# Ups_Design2.net
KiCad netlist of a schematic drawn in Altium Designer
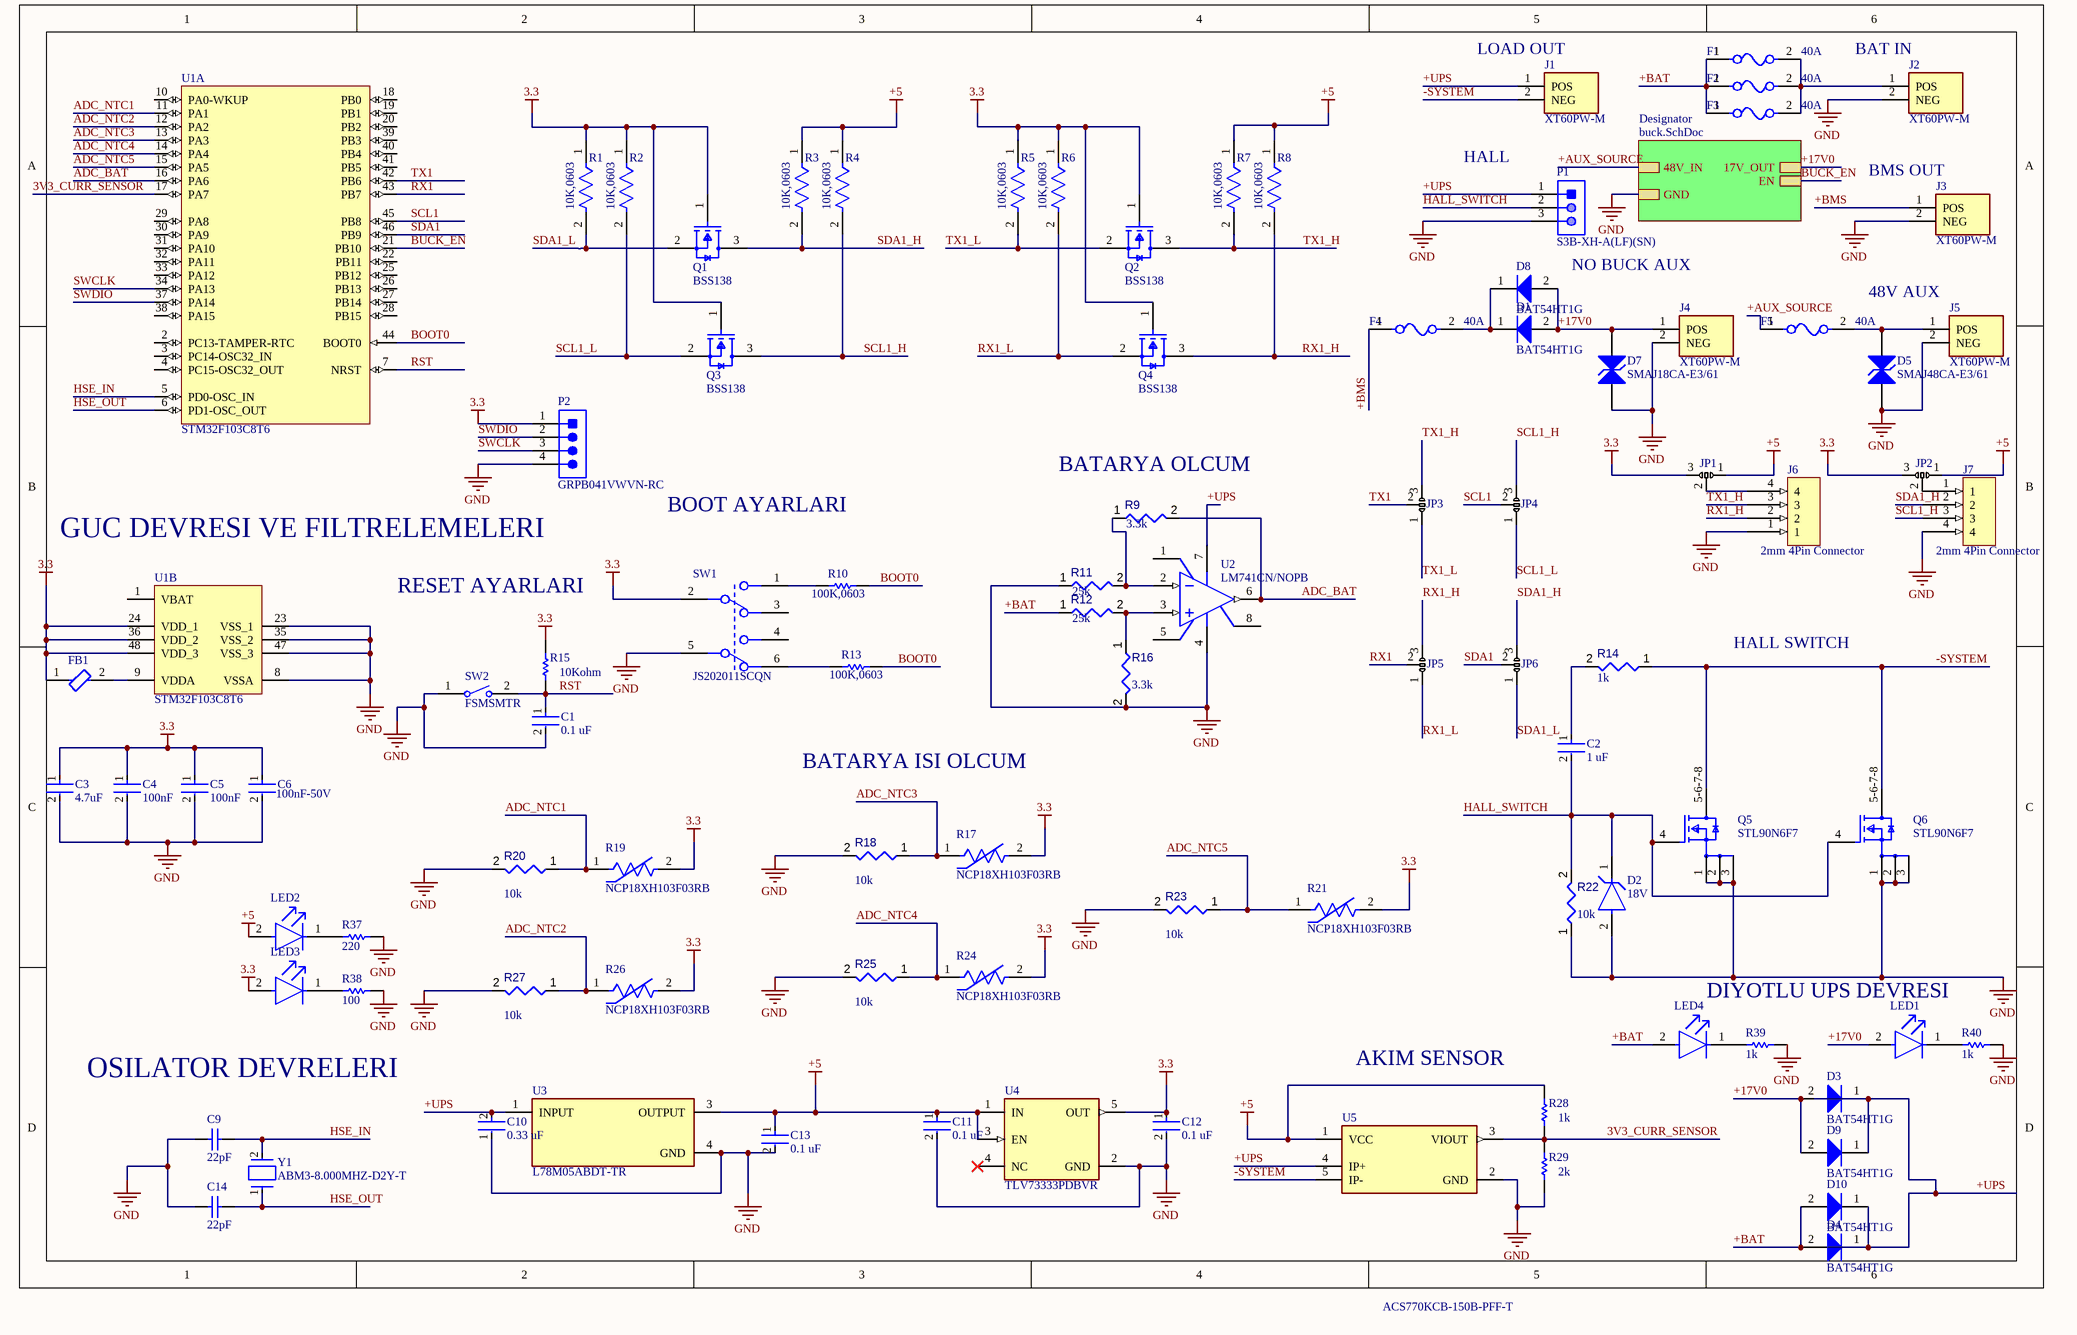
[diagram p0: Ups_Design2.SchDoc]

(export (version "E")
  (design (tool "Eeschema 10.0.6"))
  (components
    (comp (ref "C1")
      (value "0.1 uF")
      (footprint "FP-GCM188-0_1-IPC_B")
      (description "Ceramic Capacitor for Automotive 100nF  ±10% 50VDC X8L 0603 Paper T/R")
      (fields (field (name "TOLERANCE") "10%") (field (name "VOLTAGE") "50V"))
      (libsource (lib "Altium Content Vault") (part "02cd4be3c70576c341d710602a673aa"))
    )
    (comp (ref "C2")
      (value "1 uF")
      (footprint "FP-0603-L_1_6_0_15-W_0_8-IPC_C")
      (description "Ceramic Capacitor General Use 1uF ±10% 50V X7R 0603")
      (fields (field (name "TOLERANCE") "10%"))
      (libsource (lib "Altium Content Vault") (part "11868f565c42a9108669ba33697ecf6"))
    )
    (comp (ref "C3")
      (value "4.7uF")
      (footprint "FP-GRM188-0_2-IPC_C")
      (description "Chip Multilayer Ceramic Capacitors for General Purpose, 0603, 4.7uF, X5R, 15%, 10%, 35V")
      (fields (field (name "VOLTAGE") "35V") (field (name "TOLERANCE") "10%"))
      (libsource (lib "Altium Content Vault") (part "11868f565c42a9108669ba33697ecf6"))
    )
    (comp (ref "C4")
      (value "100nF")
      (footprint "FP-CGA3E-0_3-0_1-IPC_A")
      (description "Cap Ceramic 100nF 50V X7R 10% Pad SMD 0603 +125°C Automotive T/R")
      (fields (field (name "TOLERANCE") "10%") (field (name "VOLTAGE") "50V"))
      (libsource (lib "Altium Content Vault") (part "b4654b650e69147ec39a6b967a45e02"))
    )
    (comp (ref "C5")
      (value "100nF")
      (footprint "FP-CGA3E-0_3-0_1-IPC_A")
      (description "Cap Ceramic 100nF 50V X7R 10% Pad SMD 0603 +125°C Automotive T/R")
      (fields (field (name "TOLERANCE") "10%") (field (name "VOLTAGE") "50V"))
      (libsource (lib "Altium Content Vault") (part "b4654b650e69147ec39a6b967a45e02"))
    )
    (comp (ref "C6")
      (value "100nF-50V")
      (footprint "FP-CGA3E-0_3-0_1-IPC_A")
      (description "Cap Ceramic 100nF 50V X7R 10% Pad SMD 0603 +125°C Automotive T/R")
      (fields (field (name "TOLERANCE") "10%") (field (name "VOLTAGE") "50V"))
      (libsource (lib "Altium Content Vault") (part "b4654b650e69147ec39a6b967a45e02"))
    )
    (comp (ref "C9")
      (value "22pF")
      (footprint "CAPC1608X73X35LL10T15")
      (fields
        (field (name "PART NUMBER") "06033J220GBSTR")
        (field (name "MANUFACTURER") "AVX Interconnect / Elco")
      )
      (libsource (lib "Altium Content Vault") (part "CAP"))
    )
    (comp (ref "C10")
      (value "0.33 uF")
      (footprint "FP-C1608-080-0_1-IPC_B")
      (description "Multilayer Ceramic Capacitors 330nF ±10% 50V X7R SMD 0603")
      (fields (field (name "TOLERANCE") "10%") (field (name "VOLTAGE") "50V"))
      (libsource (lib "Altium Content Vault") (part "236180d848d6139a670b325ea6854c9"))
    )
    (comp (ref "C11")
      (value "0.1 uF")
      (footprint "FP-GCM188-0_1-IPC_B")
      (description "Ceramic Capacitor for Automotive 100nF  ±10% 50VDC X8L 0603 Paper T/R")
      (fields (field (name "TOLERANCE") "10%") (field (name "VOLTAGE") "50V"))
      (libsource (lib "Altium Content Vault") (part "02cd4be3c70576c341d710602a673aa"))
    )
    (comp (ref "C12")
      (value "0.1 uF")
      (footprint "FP-GCM188-0_1-IPC_B")
      (description "Ceramic Capacitor for Automotive 100nF  ±10% 50VDC X8L 0603 Paper T/R")
      (fields (field (name "TOLERANCE") "10%") (field (name "VOLTAGE") "50V"))
      (libsource (lib "Altium Content Vault") (part "02cd4be3c70576c341d710602a673aa"))
    )
    (comp (ref "C13")
      (value "0.1 uF")
      (footprint "FP-GCM188-0_1-IPC_B")
      (description "Ceramic Capacitor for Automotive 100nF  ±10% 50VDC X8L 0603 Paper T/R")
      (fields (field (name "TOLERANCE") "10%") (field (name "VOLTAGE") "50V"))
      (libsource (lib "Altium Content Vault") (part "02cd4be3c70576c341d710602a673aa"))
    )
    (comp (ref "C14")
      (value "22pF")
      (footprint "CAPC1608X73X35LL10T15")
      (fields
        (field (name "PART NUMBER") "06033J220GBSTR")
        (field (name "MANUFACTURER") "AVX Interconnect / Elco")
      )
      (libsource (lib "Altium Content Vault") (part "CAP"))
    )
    (comp (ref "D1")
      (value "BAT54HT1G")
      (footprint "ONSC-SOD-323-2-477-02_V")
      (description "Schottky Barrier Diode, 2-Pin SOD-323, Pb-Free, Tape and Reel")
      (fields (field (name "MANUFACTURER") "On Semiconductor"))
      (libsource (lib "Altium Content Vault") (part "ONSC-D-K1A2-2"))
    )
    (comp (ref "D2")
      (value "18V")
      (footprint "FP-SOD123-MFG")
      (description "DIODE ZENER 18V 500MW SOD123")
      (fields
        (field (name "OCTOPART") "https://octopart.com/bzt52c18-7-f-diodes+inc.-326572")
        (field (name "MANUFACTURER") "Diodes Inc.")
      )
      (libsource (lib "Altium Content Vault") (part "f813f71cba58e380607f5dd3caf9714"))
    )
    (comp (ref "D3")
      (value "BAT54HT1G")
      (footprint "ONSC-SOD-323-2-477-02_V")
      (description "Schottky Barrier Diode, 2-Pin SOD-323, Pb-Free, Tape and Reel")
      (fields (field (name "MANUFACTURER") "On Semiconductor"))
      (libsource (lib "Altium Content Vault") (part "ONSC-D-K1A2-2"))
    )
    (comp (ref "D4")
      (value "BAT54HT1G")
      (footprint "ONSC-SOD-323-2-477-02_V")
      (description "Schottky Barrier Diode, 2-Pin SOD-323, Pb-Free, Tape and Reel")
      (fields (field (name "MANUFACTURER") "On Semiconductor"))
      (libsource (lib "Altium Content Vault") (part "ONSC-D-K1A2-2"))
    )
    (comp (ref "D5")
      (value "SMAJ48CA-E3/61")
      (footprint "VISH-DO-214AC-2_M")
      (fields (field (name "MANUFACTURER") "Vishay Semiconductor"))
      (libsource (lib "Altium Content Vault") (part "VISH-A1A2-2"))
    )
    (comp (ref "D7")
      (value "SMAJ18CA-E3/61")
      (footprint "VISH-DO-214AC-2_L")
      (fields (field (name "MANUFACTURER") "Vishay Semiconductor"))
      (libsource (lib "Altium Content Vault") (part "VISH-A1A2-2"))
    )
    (comp (ref "D8")
      (value "BAT54HT1G")
      (footprint "ONSC-SOD-323-2-477-02_V")
      (description "Schottky Barrier Diode, 2-Pin SOD-323, Pb-Free, Tape and Reel")
      (fields (field (name "MANUFACTURER") "On Semiconductor"))
      (libsource (lib "Altium Content Vault") (part "ONSC-D-K1A2-2"))
    )
    (comp (ref "D9")
      (value "BAT54HT1G")
      (footprint "ONSC-SOD-323-2-477-02_V")
      (description "Schottky Barrier Diode, 2-Pin SOD-323, Pb-Free, Tape and Reel")
      (fields (field (name "MANUFACTURER") "On Semiconductor"))
      (libsource (lib "Altium Content Vault") (part "ONSC-D-K1A2-2"))
    )
    (comp (ref "D10")
      (value "BAT54HT1G")
      (footprint "ONSC-SOD-323-2-477-02_V")
      (description "Schottky Barrier Diode, 2-Pin SOD-323, Pb-Free, Tape and Reel")
      (fields (field (name "MANUFACTURER") "On Semiconductor"))
      (libsource (lib "Altium Content Vault") (part "ONSC-D-K1A2-2"))
    )
    (comp (ref "F1")
      (value "40A")
      (footprint "FP-0456040_DR-MFG")
      (description "FUSE BOARD MOUNT 40A 60VDC 2SMD")
      (fields
        (field (name "MANUFACTURER PART NUMBER") "0456040.DR")
        (field (name "OCTOPART") "https://octopart.com/0456040.dr-littelfuse-18189767")
      )
      (libsource (lib "Altium Content Vault") (part "5bcf9b9f640e542cf0359d10258e979"))
    )
    (comp (ref "F2")
      (value "40A")
      (footprint "FP-0456040_DR-MFG")
      (description "FUSE BOARD MOUNT 40A 60VDC 2SMD")
      (fields
        (field (name "MANUFACTURER PART NUMBER") "0456040.DR")
        (field (name "OCTOPART") "https://octopart.com/0456040.dr-littelfuse-18189767")
      )
      (libsource (lib "Altium Content Vault") (part "5bcf9b9f640e542cf0359d10258e979"))
    )
    (comp (ref "F3")
      (value "40A")
      (footprint "FP-0456040_DR-MFG")
      (description "FUSE BOARD MOUNT 40A 60VDC 2SMD")
      (fields
        (field (name "MANUFACTURER PART NUMBER") "0456040.DR")
        (field (name "OCTOPART") "https://octopart.com/0456040.dr-littelfuse-18189767")
      )
      (libsource (lib "Altium Content Vault") (part "5bcf9b9f640e542cf0359d10258e979"))
    )
    (comp (ref "F4")
      (value "40A")
      (footprint "FP-0456040_DR-MFG")
      (description "FUSE BOARD MOUNT 40A 60VDC 2SMD")
      (fields
        (field (name "MANUFACTURER PART NUMBER") "0456040.DR")
        (field (name "OCTOPART") "https://octopart.com/0456040.dr-littelfuse-18189767")
      )
      (libsource (lib "Altium Content Vault") (part "5bcf9b9f640e542cf0359d10258e979"))
    )
    (comp (ref "F5")
      (value "40A")
      (footprint "FP-0456040_DR-MFG")
      (description "FUSE BOARD MOUNT 40A 60VDC 2SMD")
      (fields
        (field (name "MANUFACTURER PART NUMBER") "0456040.DR")
        (field (name "OCTOPART") "https://octopart.com/0456040.dr-littelfuse-18189767")
      )
      (libsource (lib "Altium Content Vault") (part "5bcf9b9f640e542cf0359d10258e979"))
    )
    (comp (ref "FB1")
      (value "BLM18SG221TN1D")
      (footprint "FP-BLM18-0_15-t0_5-IPC_A")
      (description "Chip Ferrite Bead, 0603, 220Ω @ 100MHz, 25%, 0.04Ω, 2.5A")
      (fields (field (name "TOLERANCE") "25%"))
      (libsource (lib "Altium Content Vault") (part "5f30dd21d616792df468990f7003faa"))
    )
    (comp (ref "J1")
      (value "XT60PW-M")
      (footprint "AMASS_XT60PW-M")
      (description "Socket, DC supply, male, PIN: 2")
      (fields (field (name "MF") "AMASS"))
      (libsource (lib "XT60PW-M") (part "XT60PW-M"))
    )
    (comp (ref "J2")
      (value "XT60PW-M")
      (footprint "AMASS_XT60PW-M")
      (description "Socket, DC supply, male, PIN: 2")
      (fields (field (name "MF") "AMASS"))
      (libsource (lib "XT60PW-M") (part "XT60PW-M"))
    )
    (comp (ref "J3")
      (value "XT60PW-M")
      (footprint "AMASS_XT60PW-M")
      (description "Socket, DC supply, male, PIN: 2")
      (fields (field (name "MF") "AMASS"))
      (libsource (lib "XT60PW-M") (part "XT60PW-M"))
    )
    (comp (ref "J4")
      (value "XT60PW-M")
      (footprint "AMASS_XT60PW-M")
      (description "Socket, DC supply, male, PIN: 2")
      (fields (field (name "MF") "AMASS"))
      (libsource (lib "XT60PW-M") (part "XT60PW-M"))
    )
    (comp (ref "J5")
      (value "XT60PW-M")
      (footprint "AMASS_XT60PW-M")
      (description "Socket, DC supply, male, PIN: 2")
      (fields (field (name "MF") "AMASS"))
      (libsource (lib "XT60PW-M") (part "XT60PW-M"))
    )
    (comp (ref "J6")
      (value "2mm 4Pin Connector")
      (footprint "New footprint 1")
      (libsource (lib "İtü Rov") (part "New symbol 1"))
    )
    (comp (ref "J7")
      (value "2mm 4Pin Connector")
      (footprint "New footprint 1")
      (libsource (lib "") (part "New symbol 1_1"))
    )
    (comp (ref "JP1")
      (value "Jumper Pad 3P")
      (footprint "Jumper Pad 3P-Footprint-1")
      (description "3Pin Jumper Pad SWH")
      (libsource (lib "İtü Rov") (part "Jumper Pad 3P-Symbol-1"))
    )
    (comp (ref "JP2")
      (value "Jumper Pad 3P")
      (footprint "Jumper Pad 3P-Footprint-1")
      (description "3Pin Jumper Pad SWH")
      (libsource (lib "İtü Rov") (part "Jumper Pad 3P-Symbol-1"))
    )
    (comp (ref "JP3")
      (value "Jumper Pad 3P")
      (footprint "Jumper Pad 3P-Footprint-1")
      (description "3Pin Jumper Pad SWH")
      (libsource (lib "İtü Rov") (part "Jumper Pad 3P-Symbol-1"))
    )
    (comp (ref "JP4")
      (value "Jumper Pad 3P")
      (footprint "Jumper Pad 3P-Footprint-1")
      (description "3Pin Jumper Pad SWH")
      (libsource (lib "İtü Rov") (part "Jumper Pad 3P-Symbol-1"))
    )
    (comp (ref "JP5")
      (value "Jumper Pad 3P")
      (footprint "Jumper Pad 3P-Footprint-1")
      (description "3Pin Jumper Pad SWH")
      (libsource (lib "İtü Rov") (part "Jumper Pad 3P-Symbol-1"))
    )
    (comp (ref "JP6")
      (value "Jumper Pad 3P")
      (footprint "Jumper Pad 3P-Footprint-1")
      (description "3Pin Jumper Pad SWH")
      (libsource (lib "İtü Rov") (part "Jumper Pad 3P-Symbol-1"))
    )
    (comp (ref "LED1")
      (value "TLMO1000-GS08")
      (footprint "FP-6_541-5056_01-4-MFG")
      (description "LED ORANGE 0603 SMD")
      (fields
        (field (name "OCTOPART") "https://octopart.com/tlmo1000-gs08-vishay-41955669")
        (field (name "MANUFACTURER") "Vishay")
      )
      (libsource (lib "Altium Content Vault") (part "8706943c75ba83719d021d2fdc84c58"))
    )
    (comp (ref "LED2")
      (value "TLMO1000-GS08")
      (footprint "FP-6_541-5056_01-4-MFG")
      (description "LED ORANGE 0603 SMD")
      (fields
        (field (name "OCTOPART") "https://octopart.com/tlmo1000-gs08-vishay-41955669")
        (field (name "MANUFACTURER") "Vishay")
      )
      (libsource (lib "Altium Content Vault") (part "8706943c75ba83719d021d2fdc84c58"))
    )
    (comp (ref "LED3")
      (value "TLMO1000-GS08")
      (footprint "FP-6_541-5056_01-4-MFG")
      (description "LED ORANGE 0603 SMD")
      (fields
        (field (name "OCTOPART") "https://octopart.com/tlmo1000-gs08-vishay-41955669")
        (field (name "MANUFACTURER") "Vishay")
      )
      (libsource (lib "Altium Content Vault") (part "8706943c75ba83719d021d2fdc84c58"))
    )
    (comp (ref "LED4")
      (value "TLMO1000-GS08")
      (footprint "FP-6_541-5056_01-4-MFG")
      (description "LED ORANGE 0603 SMD")
      (fields
        (field (name "OCTOPART") "https://octopart.com/tlmo1000-gs08-vishay-41955669")
        (field (name "MANUFACTURER") "Vishay")
      )
      (libsource (lib "Altium Content Vault") (part "8706943c75ba83719d021d2fdc84c58"))
    )
    (comp (ref "P1")
      (value "S3B-XH-A(LF)(SN)")
      (footprint "JST-S3B-XH-A(LF)(SN)_V")
      (libsource (lib "Altium Content Vault") (part "CN-1P-M-R3"))
    )
    (comp (ref "P2")
      (value "GRPB041VWVN-RC")
      (footprint "SLIN-GRPB041VWVN-RC_V")
      (fields (field (name "MANUFACTURER") "Sullins"))
      (libsource (lib "Altium Content Vault") (part "CN-1P-M-R4"))
    )
    (comp (ref "Q1")
      (value "BSS138")
      (footprint "FP-318-08-IPC_B")
      (description "MOSFET N-CH 50V 220MA SOT-23")
      (libsource (lib "Altium Content Vault") (part "3b9c635fedb024a5347a57b145af9cc"))
    )
    (comp (ref "Q2")
      (value "BSS138")
      (footprint "FP-318-08-IPC_B")
      (description "MOSFET N-CH 50V 220MA SOT-23")
      (libsource (lib "Altium Content Vault") (part "3b9c635fedb024a5347a57b145af9cc"))
    )
    (comp (ref "Q3")
      (value "BSS138")
      (footprint "FP-318-08-IPC_B")
      (description "MOSFET N-CH 50V 220MA SOT-23")
      (libsource (lib "Altium Content Vault") (part "3b9c635fedb024a5347a57b145af9cc"))
    )
    (comp (ref "Q4")
      (value "BSS138")
      (footprint "FP-318-08-IPC_B")
      (description "MOSFET N-CH 50V 220MA SOT-23")
      (libsource (lib "Altium Content Vault") (part "3b9c635fedb024a5347a57b145af9cc"))
    )
    (comp (ref "Q5")
      (value "STL90N6F7")
      (footprint "FP-8472137_SUBCON_998G-MFG")
      (description "MOSFET N-CH 60V 90A POWERFLAT")
      (libsource (lib "Altium Content Vault") (part "7382af88e928fdc71488234cfaaf11c"))
    )
    (comp (ref "Q6")
      (value "STL90N6F7")
      (footprint "FP-8472137_SUBCON_998G-MFG")
      (description "MOSFET N-CH 60V 90A POWERFLAT")
      (libsource (lib "Altium Content Vault") (part "7382af88e928fdc71488234cfaaf11c"))
    )
    (comp (ref "R1")
      (value "10K,0603")
      (footprint "FP-ERJ3G-IPC_C")
      (description "RES SMD 10K OHM 5% 1/10W 0603")
      (fields (field (name "TOLERANCE") "5%"))
      (libsource (lib "Altium Content Vault") (part "1029c3af85768c4190bb7ad29bc67b5"))
    )
    (comp (ref "R2")
      (value "10K,0603")
      (footprint "FP-ERJ3G-IPC_C")
      (description "RES SMD 10K OHM 5% 1/10W 0603")
      (fields (field (name "TOLERANCE") "5%"))
      (libsource (lib "Altium Content Vault") (part "1029c3af85768c4190bb7ad29bc67b5"))
    )
    (comp (ref "R3")
      (value "10K,0603")
      (footprint "FP-ERJ3G-IPC_C")
      (description "RES SMD 10K OHM 5% 1/10W 0603")
      (fields (field (name "TOLERANCE") "5%"))
      (libsource (lib "Altium Content Vault") (part "1029c3af85768c4190bb7ad29bc67b5"))
    )
    (comp (ref "R4")
      (value "10K,0603")
      (footprint "FP-ERJ3G-IPC_C")
      (description "RES SMD 10K OHM 5% 1/10W 0603")
      (fields (field (name "TOLERANCE") "5%"))
      (libsource (lib "Altium Content Vault") (part "1029c3af85768c4190bb7ad29bc67b5"))
    )
    (comp (ref "R5")
      (value "10K,0603")
      (footprint "FP-ERJ3G-IPC_C")
      (description "RES SMD 10K OHM 5% 1/10W 0603")
      (fields (field (name "TOLERANCE") "5%"))
      (libsource (lib "Altium Content Vault") (part "1029c3af85768c4190bb7ad29bc67b5"))
    )
    (comp (ref "R6")
      (value "10K,0603")
      (footprint "FP-ERJ3G-IPC_C")
      (description "RES SMD 10K OHM 5% 1/10W 0603")
      (fields (field (name "TOLERANCE") "5%"))
      (libsource (lib "Altium Content Vault") (part "1029c3af85768c4190bb7ad29bc67b5"))
    )
    (comp (ref "R7")
      (value "10K,0603")
      (footprint "FP-ERJ3G-IPC_C")
      (description "RES SMD 10K OHM 5% 1/10W 0603")
      (fields (field (name "TOLERANCE") "5%"))
      (libsource (lib "Altium Content Vault") (part "1029c3af85768c4190bb7ad29bc67b5"))
    )
    (comp (ref "R8")
      (value "10K,0603")
      (footprint "FP-ERJ3G-IPC_C")
      (description "RES SMD 10K OHM 5% 1/10W 0603")
      (fields (field (name "TOLERANCE") "5%"))
      (libsource (lib "Altium Content Vault") (part "1029c3af85768c4190bb7ad29bc67b5"))
    )
    (comp (ref "R9")
      (value "3.3k")
      (footprint "RESC1608X55X25ML10T15")
      (description "Chip Resistor, 1 KOhm, +/-1%, 0.1 W, -55 to 155 degC, 0603 (1608 Metric)")
      (fields (field (name "POWER") "100mW") (field (name "TOLERANCE") "1%"))
      (libsource (lib "İtü Rov") (part "RES-2"))
    )
    (comp (ref "R10")
      (value "100K,0603")
      (footprint "RESC1608X100X25ML20T15")
      (fields (field (name "MANUFACTURER") "Vishay Dale") (field (name "PART NUMBER") "NTHS0603N01N1003JE"))
      (libsource (lib "Altium Content Vault") (part "RES"))
    )
    (comp (ref "R11")
      (value "25k")
      (footprint "RESC1608X55X25ML10T15")
      (description "Chip Resistor, 1 KOhm, +/-1%, 0.1 W, -55 to 155 degC, 0603 (1608 Metric)")
      (fields (field (name "POWER") "100mW") (field (name "TOLERANCE") "1%"))
      (libsource (lib "İtü Rov") (part "RES-2"))
    )
    (comp (ref "R12")
      (value "25k")
      (footprint "RESC1608X55X25ML10T15")
      (description "Chip Resistor, 1 KOhm, +/-1%, 0.1 W, -55 to 155 degC, 0603 (1608 Metric)")
      (fields (field (name "POWER") "100mW") (field (name "TOLERANCE") "1%"))
      (libsource (lib "İtü Rov") (part "RES-2"))
    )
    (comp (ref "R13")
      (value "100K,0603")
      (footprint "RESC1608X100X25ML20T15")
      (fields (field (name "MANUFACTURER") "Vishay Dale") (field (name "PART NUMBER") "NTHS0603N01N1003JE"))
      (libsource (lib "Altium Content Vault") (part "RES"))
    )
    (comp (ref "R14")
      (value "1k")
      (footprint "RESC1608X55X25ML10T15")
      (description "Chip Resistor, 1 KOhm, +/-1%, 0.1 W, -55 to 155 degC, 0603 (1608 Metric)")
      (fields (field (name "POWER") "100mW") (field (name "TOLERANCE") "1%"))
      (libsource (lib "İtü Rov") (part "RES-2"))
    )
    (comp (ref "R15")
      (value "10Kohm")
      (footprint "RESC1608X55X25ML10T15")
      (fields (field (name "MANUFACTURER") "Yageo") (field (name "PART NUMBER") "RC0603JR-070RA"))
      (libsource (lib "Altium Content Vault") (part "RES"))
    )
    (comp (ref "R16")
      (value "3.3k")
      (footprint "RESC1608X55X25ML10T15")
      (description "Chip Resistor, 1 KOhm, +/-1%, 0.1 W, -55 to 155 degC, 0603 (1608 Metric)")
      (fields (field (name "POWER") "100mW") (field (name "TOLERANCE") "1%"))
      (libsource (lib "İtü Rov") (part "RES-2"))
    )
    (comp (ref "R17")
      (value "NCP18XH103F03RB")
      (footprint "FP-NCP18-0_15-IPC_A")
      (description "NTC Thermistor for Temperature Sensor, 0603, 10kΩ, 1%, 0.1mA, 5V")
      (fields (field (name "TOLERANCE") "1%"))
      (libsource (lib "Altium Content Vault") (part "3b148a6ebabc5fb4d708a66c052d352"))
    )
    (comp (ref "R18")
      (value "10k")
      (footprint "RESC1608X55X25ML10T15")
      (description "Chip Resistor, 1 KOhm, +/-1%, 0.1 W, -55 to 155 degC, 0603 (1608 Metric)")
      (fields (field (name "POWER") "100mW") (field (name "TOLERANCE") "1%"))
      (libsource (lib "İtü Rov") (part "RES-2"))
    )
    (comp (ref "R19")
      (value "NCP18XH103F03RB")
      (footprint "FP-NCP18-0_15-IPC_A")
      (description "NTC Thermistor for Temperature Sensor, 0603, 10kΩ, 1%, 0.1mA, 5V")
      (fields (field (name "TOLERANCE") "1%"))
      (libsource (lib "Altium Content Vault") (part "3b148a6ebabc5fb4d708a66c052d352"))
    )
    (comp (ref "R20")
      (value "10k")
      (footprint "RESC1608X55X25ML10T15")
      (description "Chip Resistor, 1 KOhm, +/-1%, 0.1 W, -55 to 155 degC, 0603 (1608 Metric)")
      (fields (field (name "POWER") "100mW") (field (name "TOLERANCE") "1%"))
      (libsource (lib "İtü Rov") (part "RES-2"))
    )
    (comp (ref "R21")
      (value "NCP18XH103F03RB")
      (footprint "FP-NCP18-0_15-IPC_A")
      (description "NTC Thermistor for Temperature Sensor, 0603, 10kΩ, 1%, 0.1mA, 5V")
      (fields (field (name "TOLERANCE") "1%"))
      (libsource (lib "Altium Content Vault") (part "3b148a6ebabc5fb4d708a66c052d352"))
    )
    (comp (ref "R22")
      (value "10k")
      (footprint "RESC1608X55X25ML10T15")
      (description "Chip Resistor, 1 KOhm, +/-1%, 0.1 W, -55 to 155 degC, 0603 (1608 Metric)")
      (fields (field (name "POWER") "100mW") (field (name "TOLERANCE") "1%"))
      (libsource (lib "İtü Rov") (part "RES-2"))
    )
    (comp (ref "R23")
      (value "10k")
      (footprint "RESC1608X55X25ML10T15")
      (description "Chip Resistor, 1 KOhm, +/-1%, 0.1 W, -55 to 155 degC, 0603 (1608 Metric)")
      (fields (field (name "POWER") "100mW") (field (name "TOLERANCE") "1%"))
      (libsource (lib "İtü Rov") (part "RES-2"))
    )
    (comp (ref "R24")
      (value "NCP18XH103F03RB")
      (footprint "FP-NCP18-0_15-IPC_A")
      (description "NTC Thermistor for Temperature Sensor, 0603, 10kΩ, 1%, 0.1mA, 5V")
      (fields (field (name "TOLERANCE") "1%"))
      (libsource (lib "Altium Content Vault") (part "3b148a6ebabc5fb4d708a66c052d352"))
    )
    (comp (ref "R25")
      (value "10k")
      (footprint "RESC1608X55X25ML10T15")
      (description "Chip Resistor, 1 KOhm, +/-1%, 0.1 W, -55 to 155 degC, 0603 (1608 Metric)")
      (fields (field (name "POWER") "100mW") (field (name "TOLERANCE") "1%"))
      (libsource (lib "İtü Rov") (part "RES-2"))
    )
    (comp (ref "R26")
      (value "NCP18XH103F03RB")
      (footprint "FP-NCP18-0_15-IPC_A")
      (description "NTC Thermistor for Temperature Sensor, 0603, 10kΩ, 1%, 0.1mA, 5V")
      (fields (field (name "TOLERANCE") "1%"))
      (libsource (lib "Altium Content Vault") (part "3b148a6ebabc5fb4d708a66c052d352"))
    )
    (comp (ref "R27")
      (value "10k")
      (footprint "RESC1608X55X25ML10T15")
      (description "Chip Resistor, 1 KOhm, +/-1%, 0.1 W, -55 to 155 degC, 0603 (1608 Metric)")
      (fields (field (name "POWER") "100mW") (field (name "TOLERANCE") "1%"))
      (libsource (lib "İtü Rov") (part "RES-2"))
    )
    (comp (ref "R28")
      (value "1k")
      (footprint "RESC1608X55X25ML10T15")
      (fields (field (name "MANUFACTURER") "Yageo") (field (name "PART NUMBER") "RC0603JR-070RA"))
      (libsource (lib "Altium Content Vault") (part "RES"))
    )
    (comp (ref "R29")
      (value "2k")
      (footprint "RESC1608X55X25ML10T15")
      (fields (field (name "MANUFACTURER") "Yageo") (field (name "PART NUMBER") "RC0603JR-070RA"))
      (libsource (lib "Altium Content Vault") (part "RES"))
    )
    (comp (ref "R37")
      (value "220")
      (footprint "RESC1608X55X25ML10T15")
      (fields (field (name "MANUFACTURER") "Yageo") (field (name "PART NUMBER") "RC0603JR-070RA"))
      (libsource (lib "Altium Content Vault") (part "RES"))
    )
    (comp (ref "R38")
      (value "100")
      (footprint "RESC1608X55X25ML10T15")
      (fields (field (name "MANUFACTURER") "Yageo") (field (name "PART NUMBER") "RC0603JR-070RA"))
      (libsource (lib "Altium Content Vault") (part "RES"))
    )
    (comp (ref "R39")
      (value "1k")
      (footprint "RESC1608X55X25ML10T15")
      (fields (field (name "MANUFACTURER") "Yageo") (field (name "PART NUMBER") "RC0603JR-070RA"))
      (libsource (lib "Altium Content Vault") (part "RES"))
    )
    (comp (ref "R40")
      (value "1k")
      (footprint "RESC1608X55X25ML10T15")
      (fields (field (name "MANUFACTURER") "Yageo") (field (name "PART NUMBER") "RC0603JR-070RA"))
      (libsource (lib "Altium Content Vault") (part "RES"))
    )
    (comp (ref "SW1")
      (value "JS202011SCQN")
      (footprint "FP-JS202011SCQN-MFG")
      (description "SWITCH SLIDE DPDT 300MA 6V")
      (libsource (lib "Altium Content Vault") (part "ac99ea1af431c19115f5225061c5c88"))
    )
    (comp (ref "SW2")
      (value "FSMSMTR")
      (footprint "TECO-FSMSMTR_V")
      (description "FSMSM Push Button Switch, 50 mA, -35 to 85 degC, 2-Pin SMD, RoHS, Tape and Reel")
      (fields (field (name "MANUFACTURER") "TE Connectivity"))
      (libsource (lib "Altium Content Vault") (part "SW-SPST-2_C"))
    )
    (comp (ref "U1")
      (value "STM32F103C8T6")
      (footprint "STM-LQFP48_L")
      (libsource (lib "Altium Content Vault") (part "MC-ARM-STM32F103X8_B-SQ48"))
    )
    (comp (ref "U2")
      (value "LM741CN/NOPB")
      (footprint "P0008A")
      (description "Operational Amplifier, 8-pin MDIP, Pb-Free")
      (fields (field (name "MANUFACTURER") "Texas Instruments"))
      (libsource (lib "Altium Content Vault") (part "AMP-OPA-LM741-8"))
    )
    (comp (ref "U3")
      (value "L78M05ABDT-TR")
      (footprint "FP-L78M05ABDT-TR-MFG")
      (description "IC REG LINEAR 5V 500MA DPAK")
      (fields (field (name "TOLERANCE") "4%"))
      (libsource (lib "Altium Content Vault") (part "9f44cecb34f7d82ec50de3d0489c717"))
    )
    (comp (ref "U4")
      (value "TLV73333PDBVR")
      (footprint "FP-DBV0005A-MFG")
      (description "IC REG LINEAR 3.3V 300MA SOT23-5")
      (fields
        (field (name "MANUFACTURER") "Texas Instruments")
        (field (name "OCTOPART") "https://octopart.com/tlv73333pdbvr-texas+instruments-51080890")
      )
      (libsource (lib "Altium Content Vault") (part "10cdd6a861ce8db355dac0efc8b397e"))
    )
    (comp (ref "U5")
      (value "ACS770KCB-150B-PFF-T")
      (footprint "FP-CB-5-PFF-MFG")
      (description "SENSOR CURRENT HALL 150A AC/DC")
      (libsource (lib "Altium Content Vault") (part "4d0a7b7d55bf80cb027cc68505cc1c3"))
    )
    (comp (ref "Y1")
      (value "ABM3-8.000MHZ-D2Y-T")
      (footprint "FP-ABM3-MFG")
      (description "Crystal 8MHz ±20ppm 18pF SMD-2 5mm x 3.2mm")
      (fields (field (name "TOLERANCE") "20ppm"))
      (libsource (lib "Altium Content Vault") (part "c23a69dc6c9e2f18f2079038eb95dd1"))
    )
  )
  (nets
    (net (code "1") (name "+5") (class "Default")
      (node (ref "C11") (pin "1") (pinfunction "1_1") (pintype "passive"))
      (node (ref "C13") (pin "1") (pinfunction "1_1") (pintype "passive"))
      (node (ref "JP1") (pin "1") (pinfunction "1_1") (pintype "passive"))
      (node (ref "JP2") (pin "1") (pinfunction "1_1") (pintype "passive"))
      (node (ref "LED2") (pin "2") (pinfunction "A_2") (pintype "passive"))
      (node (ref "R28") (pin "2") (pinfunction "2_2") (pintype "passive"))
      (node (ref "R3") (pin "1") (pinfunction "1_1") (pintype "passive"))
      (node (ref "R4") (pin "1") (pinfunction "1_1") (pintype "passive"))
      (node (ref "R7") (pin "1") (pinfunction "1_1") (pintype "passive"))
      (node (ref "R8") (pin "1") (pinfunction "1_1") (pintype "passive"))
      (node (ref "U3") (pin "3") (pinfunction "OUTPUT_3") (pintype "power_in"))
      (node (ref "U4") (pin "1") (pinfunction "IN_1") (pintype "power_in"))
      (node (ref "U4") (pin "3") (pinfunction "EN_3") (pintype "input"))
      (node (ref "U5") (pin "1") (pinfunction "VCC_1") (pintype "power_in"))
    )
    (net (code "2") (name "/+17V0") (class "Default")
      (node (ref "D1") (pin "2") (pinfunction "A_2") (pintype "passive"))
      (node (ref "D3") (pin "2") (pinfunction "A_2") (pintype "passive"))
      (node (ref "D7") (pin "2") (pinfunction "A2_2") (pintype "passive"))
      (node (ref "D8") (pin "2") (pinfunction "A_2") (pintype "passive"))
      (node (ref "D9") (pin "2") (pinfunction "A_2") (pintype "passive"))
      (node (ref "J4") (pin "1") (pinfunction "POS_1") (pintype "passive"))
      (node (ref "LED1") (pin "2") (pinfunction "A_2") (pintype "passive"))
    )
    (net (code "3") (name "/+AUX_SOURCE") (class "Default")
      (node (ref "F5") (pin "1") (pinfunction "1_1") (pintype "passive"))
    )
    (net (code "4") (name "/+BAT") (class "Default")
      (node (ref "D10") (pin "2") (pinfunction "A_2") (pintype "passive"))
      (node (ref "D4") (pin "2") (pinfunction "A_2") (pintype "passive"))
      (node (ref "F1") (pin "1") (pinfunction "1_1") (pintype "passive"))
      (node (ref "F2") (pin "1") (pinfunction "1_1") (pintype "passive"))
      (node (ref "F3") (pin "1") (pinfunction "1_1") (pintype "passive"))
      (node (ref "LED4") (pin "2") (pinfunction "A_2") (pintype "passive"))
      (node (ref "R12") (pin "1") (pinfunction "1_1") (pintype "passive"))
    )
    (net (code "5") (name "/+BMS") (class "Default")
      (node (ref "F4") (pin "1") (pinfunction "1_1") (pintype "passive"))
      (node (ref "J3") (pin "1") (pinfunction "POS_1") (pintype "passive"))
    )
    (net (code "6") (name "/+UPS") (class "Default")
      (node (ref "C10") (pin "2") (pinfunction "2_2") (pintype "passive"))
      (node (ref "D10") (pin "1") (pinfunction "K_1") (pintype "passive"))
      (node (ref "D3") (pin "1") (pinfunction "K_1") (pintype "passive"))
      (node (ref "D4") (pin "1") (pinfunction "K_1") (pintype "passive"))
      (node (ref "D9") (pin "1") (pinfunction "K_1") (pintype "passive"))
      (node (ref "J1") (pin "1") (pinfunction "POS_1") (pintype "passive"))
      (node (ref "P1") (pin "1") (pinfunction "1_1") (pintype "passive"))
      (node (ref "U2") (pin "7") (pinfunction "V+_7") (pintype "power_in"))
      (node (ref "U3") (pin "1") (pinfunction "INPUT_1") (pintype "power_in"))
      (node (ref "U5") (pin "4") (pinfunction "IP+_4") (pintype "passive"))
    )
    (net (code "7") (name "/-SYSTEM") (class "Default")
      (node (ref "J1") (pin "2") (pinfunction "NEG_2") (pintype "passive"))
      (node (ref "Q5") (pin "5-6-7-8") (pinfunction "D_5-6-7-8") (pintype "passive"))
      (node (ref "Q6") (pin "5-6-7-8") (pinfunction "D_5-6-7-8") (pintype "passive"))
      (node (ref "R14") (pin "1") (pinfunction "1_1") (pintype "passive"))
      (node (ref "U5") (pin "5") (pinfunction "IP-_5") (pintype "passive"))
    )
    (net (code "8") (name "/3V3_CURR_SENSOR") (class "Default")
      (node (ref "R28") (pin "1") (pinfunction "1_1") (pintype "passive"))
      (node (ref "R29") (pin "2") (pinfunction "2_2") (pintype "passive"))
      (node (ref "U1") (pin "17") (pinfunction "PA7_17") (pintype "bidirectional"))
      (node (ref "U5") (pin "3") (pinfunction "VIOUT_3") (pintype "output"))
    )
    (net (code "9") (name "/ADC_BAT") (class "Default")
      (node (ref "R9") (pin "2") (pinfunction "2_2") (pintype "passive"))
      (node (ref "U1") (pin "16") (pinfunction "PA6_16") (pintype "bidirectional"))
      (node (ref "U2") (pin "6") (pinfunction "OUT_6") (pintype "output"))
    )
    (net (code "10") (name "/ADC_NTC1") (class "Default")
      (node (ref "R19") (pin "1") (pinfunction "1_1") (pintype "passive"))
      (node (ref "R20") (pin "1") (pinfunction "1_1") (pintype "passive"))
      (node (ref "U1") (pin "11") (pinfunction "PA1_11") (pintype "bidirectional"))
    )
    (net (code "11") (name "/ADC_NTC2") (class "Default")
      (node (ref "R26") (pin "1") (pinfunction "1_1") (pintype "passive"))
      (node (ref "R27") (pin "1") (pinfunction "1_1") (pintype "passive"))
      (node (ref "U1") (pin "12") (pinfunction "PA2_12") (pintype "bidirectional"))
    )
    (net (code "12") (name "/ADC_NTC3") (class "Default")
      (node (ref "R17") (pin "1") (pinfunction "1_1") (pintype "passive"))
      (node (ref "R18") (pin "1") (pinfunction "1_1") (pintype "passive"))
      (node (ref "U1") (pin "13") (pinfunction "PA3_13") (pintype "bidirectional"))
    )
    (net (code "13") (name "/ADC_NTC4") (class "Default")
      (node (ref "R24") (pin "1") (pinfunction "1_1") (pintype "passive"))
      (node (ref "R25") (pin "1") (pinfunction "1_1") (pintype "passive"))
      (node (ref "U1") (pin "14") (pinfunction "PA4_14") (pintype "bidirectional"))
    )
    (net (code "14") (name "/ADC_NTC5") (class "Default")
      (node (ref "R21") (pin "1") (pinfunction "1_1") (pintype "passive"))
      (node (ref "R23") (pin "1") (pinfunction "1_1") (pintype "passive"))
      (node (ref "U1") (pin "15") (pinfunction "PA5_15") (pintype "bidirectional"))
    )
    (net (code "15") (name "/BOOT0") (class "Default")
      (node (ref "R10") (pin "1") (pinfunction "1_1") (pintype "passive"))
      (node (ref "R13") (pin "1") (pinfunction "1_1") (pintype "passive"))
      (node (ref "U1") (pin "44") (pinfunction "BOOT0_44") (pintype "input"))
    )
    (net (code "16") (name "/BUCK_EN") (class "Default")
      (node (ref "U1") (pin "21") (pinfunction "PB10_21") (pintype "bidirectional"))
    )
    (net (code "17") (name "/HALL_SWITCH") (class "Default")
      (node (ref "C2") (pin "2") (pinfunction "2_2") (pintype "passive"))
      (node (ref "D2") (pin "1") (pinfunction "C_1") (pintype "passive"))
      (node (ref "P1") (pin "2") (pinfunction "2_2") (pintype "passive"))
      (node (ref "Q5") (pin "4") (pinfunction "G_4") (pintype "passive"))
      (node (ref "Q6") (pin "4") (pinfunction "G_4") (pintype "passive"))
      (node (ref "R22") (pin "2") (pinfunction "2_2") (pintype "passive"))
    )
    (net (code "18") (name "/HSE_IN") (class "Default")
      (node (ref "C9") (pin "2") (pinfunction "2_2") (pintype "passive"))
      (node (ref "U1") (pin "5") (pinfunction "PD0-OSC_IN_5") (pintype "bidirectional"))
      (node (ref "Y1") (pin "2") (pinfunction "2_2") (pintype "passive"))
    )
    (net (code "19") (name "/HSE_OUT") (class "Default")
      (node (ref "C14") (pin "2") (pinfunction "2_2") (pintype "passive"))
      (node (ref "U1") (pin "6") (pinfunction "PD1-OSC_OUT_6") (pintype "bidirectional"))
      (node (ref "Y1") (pin "1") (pinfunction "1_1") (pintype "passive"))
    )
    (net (code "20") (name "/RST") (class "Default")
      (node (ref "C1") (pin "1") (pinfunction "1_1") (pintype "passive"))
      (node (ref "R15") (pin "1") (pinfunction "1_1") (pintype "passive"))
      (node (ref "SW2") (pin "2") (pinfunction "2_2") (pintype "passive"))
      (node (ref "U1") (pin "7") (pinfunction "NRST_7") (pintype "bidirectional"))
    )
    (net (code "21") (name "/RX1") (class "Default")
      (node (ref "JP5") (pin "2") (pinfunction "2_2") (pintype "passive"))
      (node (ref "U1") (pin "43") (pinfunction "PB7_43") (pintype "bidirectional"))
    )
    (net (code "22") (name "/RX1_H") (class "Default")
      (node (ref "J6") (pin "2") (pinfunction "2_2") (pintype "input"))
      (node (ref "JP5") (pin "3") (pinfunction "2_3") (pintype "passive"))
      (node (ref "Q4") (pin "3") (pinfunction "D_3") (pintype "passive"))
      (node (ref "R8") (pin "2") (pinfunction "2_2") (pintype "passive"))
    )
    (net (code "23") (name "/RX1_L") (class "Default")
      (node (ref "JP5") (pin "1") (pinfunction "1_1") (pintype "passive"))
      (node (ref "Q4") (pin "2") (pinfunction "S_2") (pintype "passive"))
      (node (ref "R6") (pin "2") (pinfunction "2_2") (pintype "passive"))
    )
    (net (code "24") (name "/SCL1") (class "Default")
      (node (ref "JP4") (pin "2") (pinfunction "2_2") (pintype "passive"))
      (node (ref "U1") (pin "45") (pinfunction "PB8_45") (pintype "bidirectional"))
    )
    (net (code "25") (name "/SCL1_H") (class "Default")
      (node (ref "J7") (pin "3") (pinfunction "3_3") (pintype "input"))
      (node (ref "JP4") (pin "3") (pinfunction "2_3") (pintype "passive"))
      (node (ref "Q3") (pin "3") (pinfunction "D_3") (pintype "passive"))
      (node (ref "R4") (pin "2") (pinfunction "2_2") (pintype "passive"))
    )
    (net (code "26") (name "/SCL1_L") (class "Default")
      (node (ref "JP4") (pin "1") (pinfunction "1_1") (pintype "passive"))
      (node (ref "Q3") (pin "2") (pinfunction "S_2") (pintype "passive"))
      (node (ref "R2") (pin "2") (pinfunction "2_2") (pintype "passive"))
    )
    (net (code "27") (name "/SDA1") (class "Default")
      (node (ref "JP6") (pin "2") (pinfunction "2_2") (pintype "passive"))
      (node (ref "U1") (pin "46") (pinfunction "PB9_46") (pintype "bidirectional"))
    )
    (net (code "28") (name "/SDA1_H") (class "Default")
      (node (ref "J7") (pin "2") (pinfunction "2_2") (pintype "input"))
      (node (ref "JP6") (pin "3") (pinfunction "2_3") (pintype "passive"))
      (node (ref "Q1") (pin "3") (pinfunction "D_3") (pintype "passive"))
      (node (ref "R3") (pin "2") (pinfunction "2_2") (pintype "passive"))
    )
    (net (code "29") (name "/SDA1_L") (class "Default")
      (node (ref "JP6") (pin "1") (pinfunction "1_1") (pintype "passive"))
      (node (ref "Q1") (pin "2") (pinfunction "S_2") (pintype "passive"))
      (node (ref "R1") (pin "2") (pinfunction "2_2") (pintype "passive"))
    )
    (net (code "30") (name "/SWCLK") (class "Default")
      (node (ref "P2") (pin "3") (pinfunction "3_3") (pintype "passive"))
      (node (ref "U1") (pin "34") (pinfunction "PA13_34") (pintype "bidirectional"))
    )
    (net (code "31") (name "/SWDIO") (class "Default")
      (node (ref "P2") (pin "2") (pinfunction "2_2") (pintype "passive"))
      (node (ref "U1") (pin "37") (pinfunction "PA14_37") (pintype "bidirectional"))
    )
    (net (code "32") (name "/TX1") (class "Default")
      (node (ref "JP3") (pin "2") (pinfunction "2_2") (pintype "passive"))
      (node (ref "U1") (pin "42") (pinfunction "PB6_42") (pintype "bidirectional"))
    )
    (net (code "33") (name "/TX1_H") (class "Default")
      (node (ref "J6") (pin "3") (pinfunction "3_3") (pintype "input"))
      (node (ref "JP3") (pin "3") (pinfunction "2_3") (pintype "passive"))
      (node (ref "Q2") (pin "3") (pinfunction "D_3") (pintype "passive"))
      (node (ref "R7") (pin "2") (pinfunction "2_2") (pintype "passive"))
    )
    (net (code "34") (name "/TX1_L") (class "Default")
      (node (ref "JP3") (pin "1") (pinfunction "1_1") (pintype "passive"))
      (node (ref "Q2") (pin "2") (pinfunction "S_2") (pintype "passive"))
      (node (ref "R5") (pin "2") (pinfunction "2_2") (pintype "passive"))
    )
    (net (code "35") (name "3.3") (class "Default")
      (node (ref "C12") (pin "1") (pinfunction "1_1") (pintype "passive"))
      (node (ref "C3") (pin "1") (pinfunction "1_1") (pintype "passive"))
      (node (ref "C4") (pin "1") (pinfunction "1_1") (pintype "passive"))
      (node (ref "C5") (pin "1") (pinfunction "1_1") (pintype "passive"))
      (node (ref "C6") (pin "1") (pinfunction "1_1") (pintype "passive"))
      (node (ref "FB1") (pin "1") (pinfunction "1_1") (pintype "passive"))
      (node (ref "JP1") (pin "3") (pinfunction "2_3") (pintype "passive"))
      (node (ref "JP2") (pin "3") (pinfunction "2_3") (pintype "passive"))
      (node (ref "LED3") (pin "2") (pinfunction "A_2") (pintype "passive"))
      (node (ref "P2") (pin "1") (pinfunction "1_1") (pintype "passive"))
      (node (ref "Q1") (pin "1") (pinfunction "G_1") (pintype "passive"))
      (node (ref "Q2") (pin "1") (pinfunction "G_1") (pintype "passive"))
      (node (ref "Q3") (pin "1") (pinfunction "G_1") (pintype "passive"))
      (node (ref "Q4") (pin "1") (pinfunction "G_1") (pintype "passive"))
      (node (ref "R1") (pin "1") (pinfunction "1_1") (pintype "passive"))
      (node (ref "R15") (pin "2") (pinfunction "2_2") (pintype "passive"))
      (node (ref "R17") (pin "2") (pinfunction "2_2") (pintype "passive"))
      (node (ref "R19") (pin "2") (pinfunction "2_2") (pintype "passive"))
      (node (ref "R2") (pin "1") (pinfunction "1_1") (pintype "passive"))
      (node (ref "R21") (pin "2") (pinfunction "2_2") (pintype "passive"))
      (node (ref "R24") (pin "2") (pinfunction "2_2") (pintype "passive"))
      (node (ref "R26") (pin "2") (pinfunction "2_2") (pintype "passive"))
      (node (ref "R5") (pin "1") (pinfunction "1_1") (pintype "passive"))
      (node (ref "R6") (pin "1") (pinfunction "1_1") (pintype "passive"))
      (node (ref "SW1") (pin "2") (pinfunction "2_2") (pintype "passive"))
      (node (ref "U1") (pin "24") (pinfunction "VDD_1_24") (pintype "power_in"))
      (node (ref "U1") (pin "36") (pinfunction "VDD_2_36") (pintype "power_in"))
      (node (ref "U1") (pin "48") (pinfunction "VDD_3_48") (pintype "power_in"))
      (node (ref "U4") (pin "5") (pinfunction "OUT_5") (pintype "output"))
    )
    (net (code "36") (name "GND") (class "Default")
      (node (ref "C1") (pin "2") (pinfunction "2_2") (pintype "passive"))
      (node (ref "C10") (pin "1") (pinfunction "1_1") (pintype "passive"))
      (node (ref "C11") (pin "2") (pinfunction "2_2") (pintype "passive"))
      (node (ref "C12") (pin "2") (pinfunction "2_2") (pintype "passive"))
      (node (ref "C13") (pin "2") (pinfunction "2_2") (pintype "passive"))
      (node (ref "C14") (pin "1") (pinfunction "1_1") (pintype "passive"))
      (node (ref "C3") (pin "2") (pinfunction "2_2") (pintype "passive"))
      (node (ref "C4") (pin "2") (pinfunction "2_2") (pintype "passive"))
      (node (ref "C5") (pin "2") (pinfunction "2_2") (pintype "passive"))
      (node (ref "C6") (pin "2") (pinfunction "2_2") (pintype "passive"))
      (node (ref "C9") (pin "1") (pinfunction "1_1") (pintype "passive"))
      (node (ref "D2") (pin "2") (pinfunction "A_2") (pintype "passive"))
      (node (ref "D5") (pin "1") (pinfunction "A1_1") (pintype "passive"))
      (node (ref "D7") (pin "1") (pinfunction "A1_1") (pintype "passive"))
      (node (ref "J2") (pin "2") (pinfunction "NEG_2") (pintype "passive"))
      (node (ref "J3") (pin "2") (pinfunction "NEG_2") (pintype "passive"))
      (node (ref "J4") (pin "2") (pinfunction "NEG_2") (pintype "passive"))
      (node (ref "J5") (pin "2") (pinfunction "NEG_2") (pintype "passive"))
      (node (ref "J6") (pin "1") (pinfunction "1_1") (pintype "input"))
      (node (ref "J7") (pin "4") (pinfunction "4_4") (pintype "input"))
      (node (ref "P1") (pin "3") (pinfunction "3_3") (pintype "passive"))
      (node (ref "P2") (pin "4") (pinfunction "4_4") (pintype "passive"))
      (node (ref "Q5") (pin "1") (pinfunction "S_1") (pintype "passive"))
      (node (ref "Q5") (pin "2") (pinfunction "S_2") (pintype "passive"))
      (node (ref "Q5") (pin "3") (pinfunction "S_3") (pintype "passive"))
      (node (ref "Q6") (pin "1") (pinfunction "S_1") (pintype "passive"))
      (node (ref "Q6") (pin "2") (pinfunction "S_2") (pintype "passive"))
      (node (ref "Q6") (pin "3") (pinfunction "S_3") (pintype "passive"))
      (node (ref "R11") (pin "1") (pinfunction "1_1") (pintype "passive"))
      (node (ref "R16") (pin "2") (pinfunction "2_2") (pintype "passive"))
      (node (ref "R18") (pin "2") (pinfunction "2_2") (pintype "passive"))
      (node (ref "R20") (pin "2") (pinfunction "2_2") (pintype "passive"))
      (node (ref "R22") (pin "1") (pinfunction "1_1") (pintype "passive"))
      (node (ref "R23") (pin "2") (pinfunction "2_2") (pintype "passive"))
      (node (ref "R25") (pin "2") (pinfunction "2_2") (pintype "passive"))
      (node (ref "R27") (pin "2") (pinfunction "2_2") (pintype "passive"))
      (node (ref "R29") (pin "1") (pinfunction "1_1") (pintype "passive"))
      (node (ref "R37") (pin "1") (pinfunction "1_1") (pintype "passive"))
      (node (ref "R38") (pin "1") (pinfunction "1_1") (pintype "passive"))
      (node (ref "R39") (pin "1") (pinfunction "1_1") (pintype "passive"))
      (node (ref "R40") (pin "1") (pinfunction "1_1") (pintype "passive"))
      (node (ref "SW1") (pin "5") (pinfunction "5_5") (pintype "passive"))
      (node (ref "SW2") (pin "1") (pinfunction "1_1") (pintype "passive"))
      (node (ref "U1") (pin "23") (pinfunction "VSS_1_23") (pintype "power_in"))
      (node (ref "U1") (pin "35") (pinfunction "VSS_2_35") (pintype "power_in"))
      (node (ref "U1") (pin "47") (pinfunction "VSS_3_47") (pintype "power_in"))
      (node (ref "U1") (pin "8") (pinfunction "VSSA_8") (pintype "power_in"))
      (node (ref "U2") (pin "4") (pinfunction "V-_4") (pintype "power_in"))
      (node (ref "U3") (pin "4") (pinfunction "GND_4") (pintype "power_in"))
      (node (ref "U4") (pin "2") (pinfunction "GND_2") (pintype "power_in"))
      (node (ref "U5") (pin "2") (pinfunction "GND_2") (pintype "power_in"))
    )
    (net (code "37") (name "Net-(C2-Pad1)") (class "Default")
      (node (ref "C2") (pin "1") (pinfunction "1_1") (pintype "passive"))
      (node (ref "R14") (pin "2") (pinfunction "2_2") (pintype "passive"))
    )
    (net (code "38") (name "Net-(D1-K)") (class "Default")
      (node (ref "D1") (pin "1") (pinfunction "K_1") (pintype "passive"))
      (node (ref "D8") (pin "1") (pinfunction "K_1") (pintype "passive"))
      (node (ref "F4") (pin "2") (pinfunction "2_2") (pintype "passive"))
    )
    (net (code "39") (name "Net-(D5-A2)") (class "Default")
      (node (ref "D5") (pin "2") (pinfunction "A2_2") (pintype "passive"))
      (node (ref "F5") (pin "2") (pinfunction "2_2") (pintype "passive"))
      (node (ref "J5") (pin "1") (pinfunction "POS_1") (pintype "passive"))
    )
    (net (code "40") (name "Net-(J2-POS)") (class "Default")
      (node (ref "F1") (pin "2") (pinfunction "2_2") (pintype "passive"))
      (node (ref "F2") (pin "2") (pinfunction "2_2") (pintype "passive"))
      (node (ref "F3") (pin "2") (pinfunction "2_2") (pintype "passive"))
      (node (ref "J2") (pin "1") (pinfunction "POS_1") (pintype "passive"))
    )
    (net (code "41") (name "Net-(J6-Pad4)") (class "Default")
      (node (ref "J6") (pin "4") (pinfunction "4_4") (pintype "input"))
      (node (ref "JP1") (pin "2") (pinfunction "2_2") (pintype "passive"))
    )
    (net (code "42") (name "Net-(J7-Pad1)") (class "Default")
      (node (ref "J7") (pin "1") (pinfunction "1_1") (pintype "input"))
      (node (ref "JP2") (pin "2") (pinfunction "2_2") (pintype "passive"))
    )
    (net (code "43") (name "Net-(LED1-C)") (class "Default")
      (node (ref "LED1") (pin "1") (pinfunction "C_1") (pintype "passive"))
      (node (ref "R40") (pin "2") (pinfunction "2_2") (pintype "passive"))
    )
    (net (code "44") (name "Net-(LED2-C)") (class "Default")
      (node (ref "LED2") (pin "1") (pinfunction "C_1") (pintype "passive"))
      (node (ref "R37") (pin "2") (pinfunction "2_2") (pintype "passive"))
    )
    (net (code "45") (name "Net-(LED3-C)") (class "Default")
      (node (ref "LED3") (pin "1") (pinfunction "C_1") (pintype "passive"))
      (node (ref "R38") (pin "2") (pinfunction "2_2") (pintype "passive"))
    )
    (net (code "46") (name "Net-(LED4-C)") (class "Default")
      (node (ref "LED4") (pin "1") (pinfunction "C_1") (pintype "passive"))
      (node (ref "R39") (pin "2") (pinfunction "2_2") (pintype "passive"))
    )
    (net (code "47") (name "Net-(R10-Pad2)") (class "Default")
      (node (ref "R10") (pin "2") (pinfunction "2_2") (pintype "passive"))
      (node (ref "SW1") (pin "1") (pinfunction "1_1") (pintype "passive"))
    )
    (net (code "48") (name "Net-(R13-Pad2)") (class "Default")
      (node (ref "R13") (pin "2") (pinfunction "2_2") (pintype "passive"))
      (node (ref "SW1") (pin "6") (pinfunction "6_6") (pintype "passive"))
    )
    (net (code "49") (name "Net-(U1B-VDDA)") (class "Default")
      (node (ref "FB1") (pin "2") (pinfunction "2_2") (pintype "passive"))
      (node (ref "U1") (pin "9") (pinfunction "VDDA_9") (pintype "power_in"))
    )
    (net (code "50") (name "Net-(U2-IN+)") (class "Default")
      (node (ref "R12") (pin "2") (pinfunction "2_2") (pintype "passive"))
      (node (ref "R16") (pin "1") (pinfunction "1_1") (pintype "passive"))
      (node (ref "U2") (pin "3") (pinfunction "IN+_3") (pintype "input"))
    )
    (net (code "51") (name "Net-(U2-IN-)") (class "Default")
      (node (ref "R11") (pin "2") (pinfunction "2_2") (pintype "passive"))
      (node (ref "R9") (pin "1") (pinfunction "1_1") (pintype "passive"))
      (node (ref "U2") (pin "2") (pinfunction "IN-_2") (pintype "input"))
    )
    (net (code "52") (name "unconnected-(SW1-Pad3)") (class "Default")
      (node (ref "SW1") (pin "3") (pinfunction "3_3") (pintype "passive"))
    )
    (net (code "53") (name "unconnected-(SW1-Pad4)") (class "Default")
      (node (ref "SW1") (pin "4") (pinfunction "4_4") (pintype "passive"))
    )
    (net (code "54") (name "unconnected-(U1A-PA0-WKUP-Pad10)") (class "Default")
      (node (ref "U1") (pin "10") (pinfunction "PA0-WKUP_10") (pintype "bidirectional"))
    )
    (net (code "55") (name "unconnected-(U1A-PA8-Pad29)") (class "Default")
      (node (ref "U1") (pin "29") (pinfunction "PA8_29") (pintype "bidirectional"))
    )
    (net (code "56") (name "unconnected-(U1A-PA9-Pad30)") (class "Default")
      (node (ref "U1") (pin "30") (pinfunction "PA9_30") (pintype "bidirectional"))
    )
    (net (code "57") (name "unconnected-(U1A-PA10-Pad31)") (class "Default")
      (node (ref "U1") (pin "31") (pinfunction "PA10_31") (pintype "bidirectional"))
    )
    (net (code "58") (name "unconnected-(U1A-PA11-Pad32)") (class "Default")
      (node (ref "U1") (pin "32") (pinfunction "PA11_32") (pintype "bidirectional"))
    )
    (net (code "59") (name "unconnected-(U1A-PA12-Pad33)") (class "Default")
      (node (ref "U1") (pin "33") (pinfunction "PA12_33") (pintype "bidirectional"))
    )
    (net (code "60") (name "unconnected-(U1A-PA15-Pad38)") (class "Default")
      (node (ref "U1") (pin "38") (pinfunction "PA15_38") (pintype "bidirectional"))
    )
    (net (code "61") (name "unconnected-(U1A-PB0-Pad18)") (class "Default")
      (node (ref "U1") (pin "18") (pinfunction "PB0_18") (pintype "bidirectional"))
    )
    (net (code "62") (name "unconnected-(U1A-PB1-Pad19)") (class "Default")
      (node (ref "U1") (pin "19") (pinfunction "PB1_19") (pintype "bidirectional"))
    )
    (net (code "63") (name "unconnected-(U1A-PB2-Pad20)") (class "Default")
      (node (ref "U1") (pin "20") (pinfunction "PB2_20") (pintype "bidirectional"))
    )
    (net (code "64") (name "unconnected-(U1A-PB3-Pad39)") (class "Default")
      (node (ref "U1") (pin "39") (pinfunction "PB3_39") (pintype "bidirectional"))
    )
    (net (code "65") (name "unconnected-(U1A-PB4-Pad40)") (class "Default")
      (node (ref "U1") (pin "40") (pinfunction "PB4_40") (pintype "bidirectional"))
    )
    (net (code "66") (name "unconnected-(U1A-PB5-Pad41)") (class "Default")
      (node (ref "U1") (pin "41") (pinfunction "PB5_41") (pintype "bidirectional"))
    )
    (net (code "67") (name "unconnected-(U1A-PB11-Pad22)") (class "Default")
      (node (ref "U1") (pin "22") (pinfunction "PB11_22") (pintype "bidirectional"))
    )
    (net (code "68") (name "unconnected-(U1A-PB12-Pad25)") (class "Default")
      (node (ref "U1") (pin "25") (pinfunction "PB12_25") (pintype "bidirectional"))
    )
    (net (code "69") (name "unconnected-(U1A-PB13-Pad26)") (class "Default")
      (node (ref "U1") (pin "26") (pinfunction "PB13_26") (pintype "bidirectional"))
    )
    (net (code "70") (name "unconnected-(U1A-PB14-Pad27)") (class "Default")
      (node (ref "U1") (pin "27") (pinfunction "PB14_27") (pintype "bidirectional"))
    )
    (net (code "71") (name "unconnected-(U1A-PB15-Pad28)") (class "Default")
      (node (ref "U1") (pin "28") (pinfunction "PB15_28") (pintype "bidirectional"))
    )
    (net (code "72") (name "unconnected-(U1A-PC13-TAMPER-RTC-Pad2)") (class "Default")
      (node (ref "U1") (pin "2") (pinfunction "PC13-TAMPER-RTC_2") (pintype "bidirectional"))
    )
    (net (code "73") (name "unconnected-(U1A-PC14-OSC32_IN-Pad3)") (class "Default")
      (node (ref "U1") (pin "3") (pinfunction "PC14-OSC32_IN_3") (pintype "bidirectional"))
    )
    (net (code "74") (name "unconnected-(U1A-PC15-OSC32_OUT-Pad4)") (class "Default")
      (node (ref "U1") (pin "4") (pinfunction "PC15-OSC32_OUT_4") (pintype "bidirectional"))
    )
    (net (code "75") (name "unconnected-(U1B-VBAT-Pad1)") (class "Default")
      (node (ref "U1") (pin "1") (pinfunction "VBAT_1") (pintype "power_in"))
    )
    (net (code "76") (name "unconnected-(U2-NC-Pad8)") (class "Default")
      (node (ref "U2") (pin "8") (pinfunction "NC_8") (pintype "passive"))
    )
    (net (code "77") (name "unconnected-(U2-OFS_NULL-Pad1)") (class "Default")
      (node (ref "U2") (pin "1") (pinfunction "OFS_NULL_1") (pintype "passive"))
    )
    (net (code "78") (name "unconnected-(U2-OFS_NULL-Pad5)") (class "Default")
      (node (ref "U2") (pin "5") (pinfunction "OFS_NULL_5") (pintype "passive"))
    )
    (net (code "79") (name "unconnected-(U4-NC-Pad4)") (class "Default")
      (node (ref "U4") (pin "4") (pinfunction "NC_4") (pintype "passive+no_connect"))
    )
  )
)
